# Fuente3_3VDC.net
KiCad netlist of a schematic drawn in Altium Designer
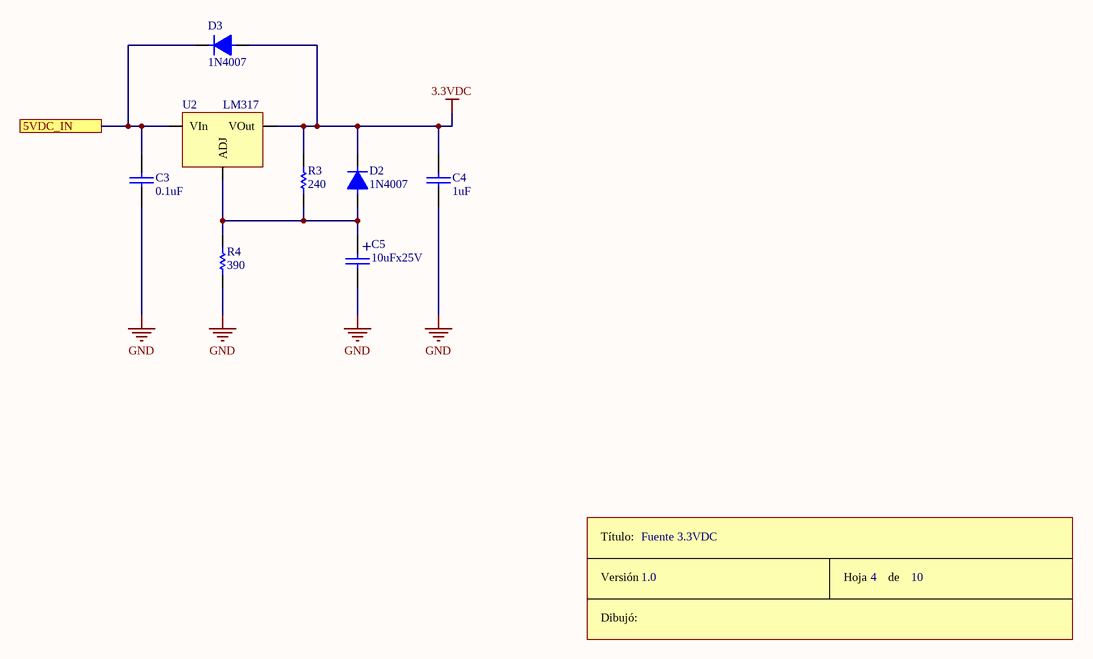
[diagram p0: Fuente3.3VDC.SchDoc]

(export (version "E")
  (design (tool "Eeschema 10.0.6"))
  (components
    (comp (ref "C3") (value "0.1uF") (footprint "CAP100") (libsource (lib "LIBEBAL") (part "CAP")))
    (comp (ref "C4") (value "1uF") (footprint "CAP200") (libsource (lib "LIBEBAL") (part "CAP")))
    (comp (ref "C5") (value "10uFx25V") (footprint "CAP100RP") (libsource (lib "LIBEBAL") (part "CAPPOL")))
    (comp (ref "D2") (value "1N4007") (footprint "DO41") (libsource (lib "LIBEBAL") (part "DIODO")))
    (comp (ref "D3") (value "1N4007") (footprint "DO41") (libsource (lib "LIBEBAL") (part "DIODO")))
    (comp (ref "R3") (value "240") (footprint "RES400") (libsource (lib "LIBEBAL") (part "RES")))
    (comp (ref "R4") (value "390") (footprint "RES400") (libsource (lib "LIBEBAL") (part "RES")))
    (comp (ref "ROT2") (value "Rótulo") (libsource (lib "LIB PIO IX") (part "Rótulo")))
    (comp (ref "U2")
      (value "LM317")
      (footprint "TO-220 H")
      (description "IC REG ADJ 1.5A 3 TERM TO-220")
      (libsource (lib "LIBEBAL") (part "LM317"))
    )
  )
  (nets
    (net (code "1") (name "/5VDC_IN") (class "Default")
      (node (ref "C3") (pin "1") (pinfunction "1_1") (pintype "passive"))
      (node (ref "D3") (pin "2") (pinfunction "2_2") (pintype "passive"))
      (node (ref "U2") (pin "3") (pinfunction "VIn_3") (pintype "passive"))
    )
    (net (code "2") (name "3.3VDC") (class "Default")
      (node (ref "C4") (pin "1") (pinfunction "1_1") (pintype "passive"))
      (node (ref "D2") (pin "2") (pinfunction "2_2") (pintype "passive"))
      (node (ref "D3") (pin "1") (pinfunction "1_1") (pintype "passive"))
      (node (ref "R3") (pin "2") (pinfunction "2_2") (pintype "passive"))
      (node (ref "U2") (pin "2") (pinfunction "VOut_2") (pintype "passive"))
    )
    (net (code "3") (name "GND") (class "Default")
      (node (ref "C3") (pin "2") (pinfunction "2_2") (pintype "passive"))
      (node (ref "C4") (pin "2") (pinfunction "2_2") (pintype "passive"))
      (node (ref "C5") (pin "2") (pinfunction "2_2") (pintype "passive"))
      (node (ref "R4") (pin "1") (pinfunction "1_1") (pintype "passive"))
    )
    (net (code "4") (name "Net-(U2-ADJ)") (class "Default")
      (node (ref "C5") (pin "1") (pinfunction "1_1") (pintype "passive"))
      (node (ref "D2") (pin "1") (pinfunction "1_1") (pintype "passive"))
      (node (ref "R3") (pin "1") (pinfunction "1_1") (pintype "passive"))
      (node (ref "R4") (pin "2") (pinfunction "2_2") (pintype "passive"))
      (node (ref "U2") (pin "1") (pinfunction "ADJ_1") (pintype "passive"))
    )
  )
)
